# Power.net
KiCad netlist of a schematic drawn in Altium Designer
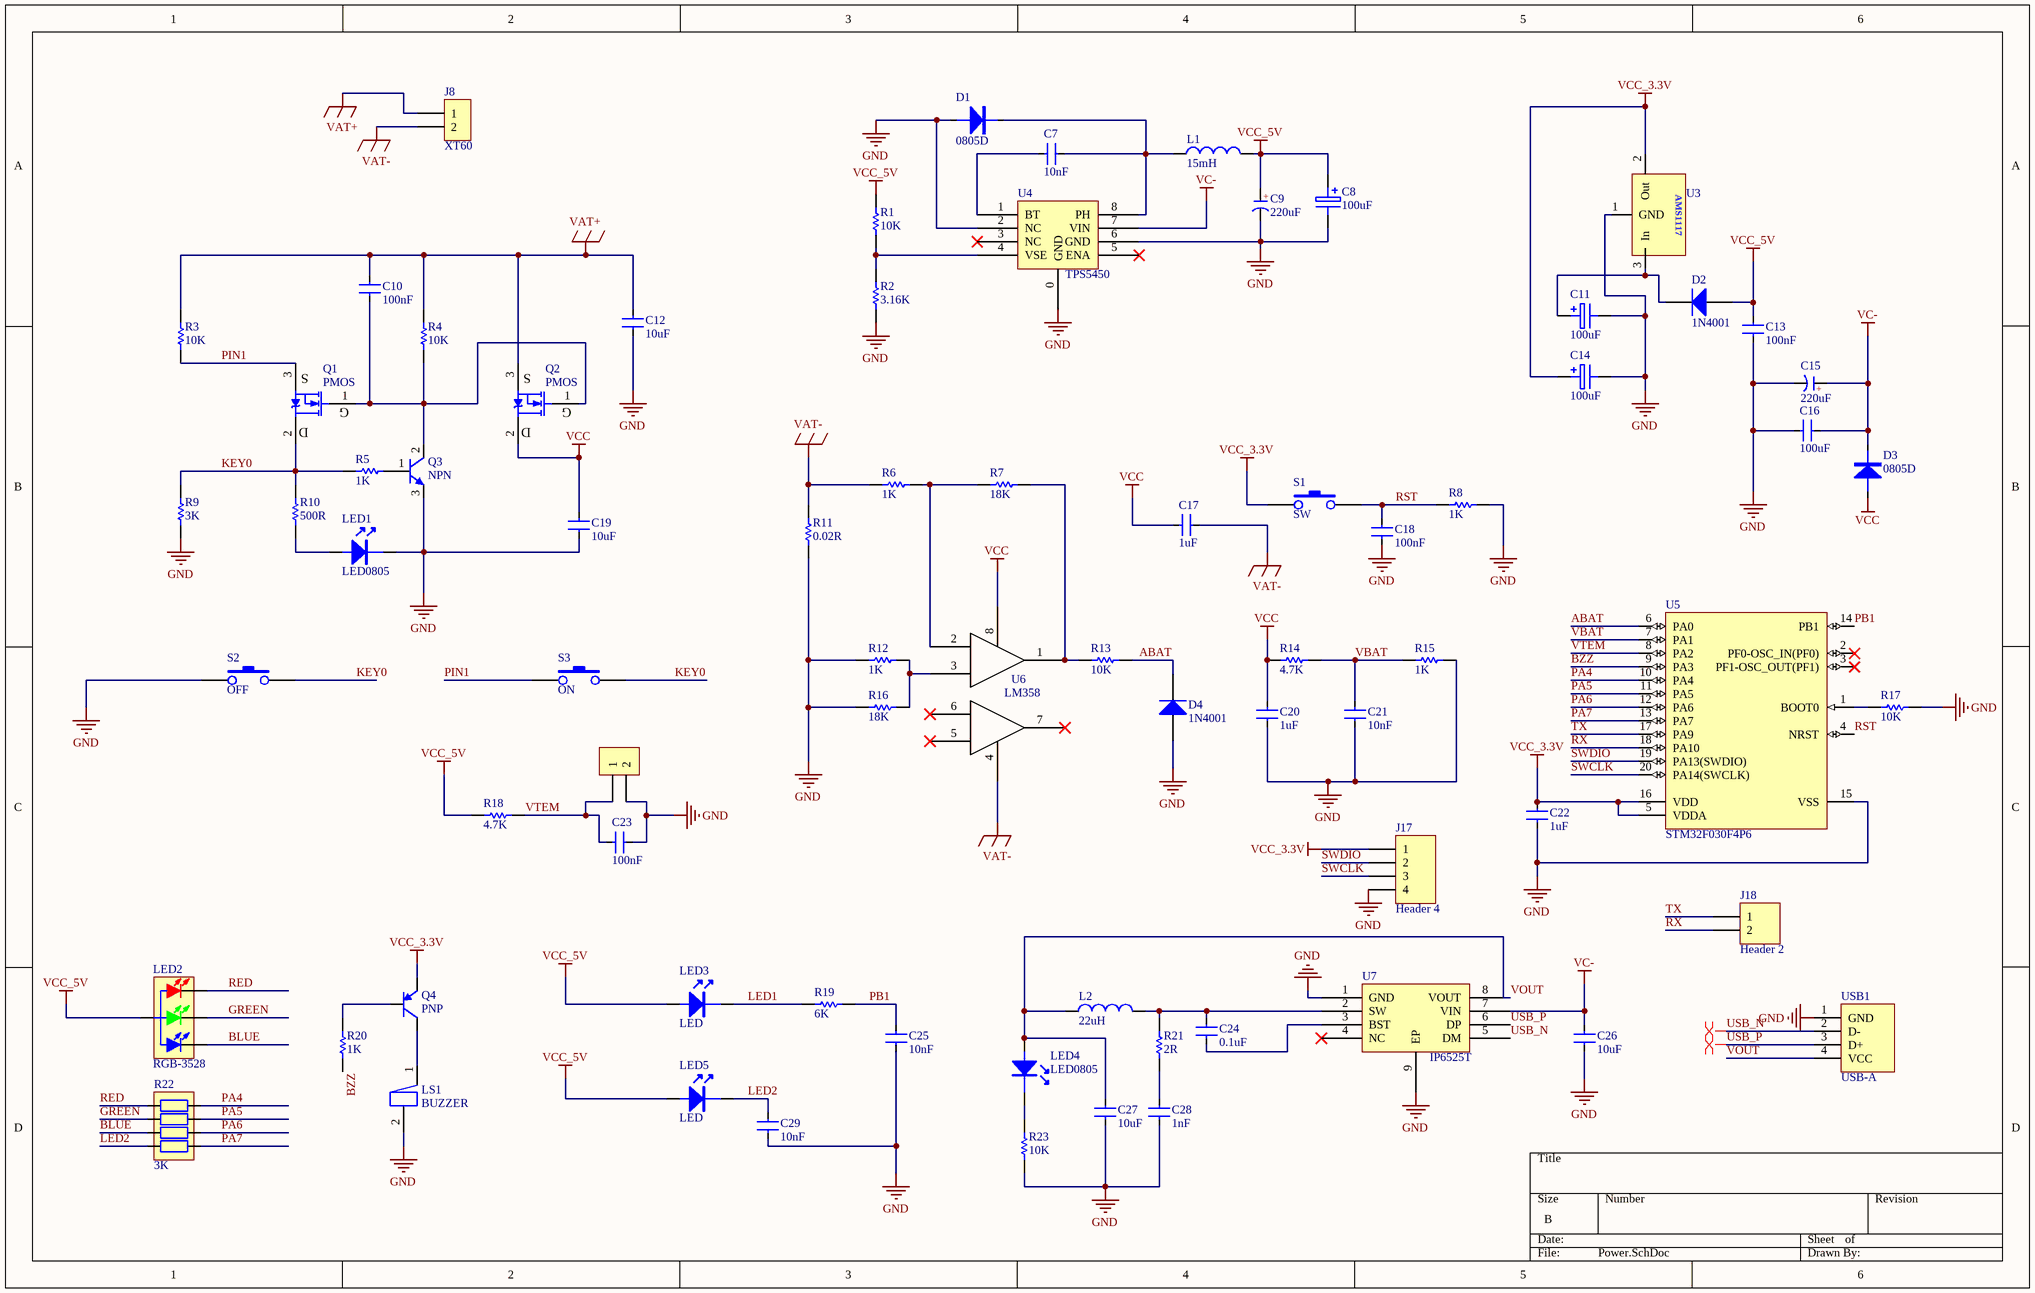
[diagram p0: Power.SchDoc]

(export (version "E")
  (design (tool "Eeschema 10.0.6"))
  (components
    (comp (ref "C7") (value "10nF") (footprint "0603_C") (libsource (lib "电容") (part "C0805")))
    (comp (ref "C8")
      (value "100uF")
      (footprint "CASE-C_6032")
      (description "电解电容")
      (libsource (lib "常用器件") (part "CAP-E"))
    )
    (comp (ref "C9")
      (value "220uF")
      (footprint "CASE-E_7343")
      (description "直插固态电容")
      (fields (field (name "版权归属") "源创客"))
      (libsource (lib "") (part "C-CS_1"))
    )
    (comp (ref "C10") (value "100nF") (footprint "0603_C") (libsource (lib "电容") (part "C0805")))
    (comp (ref "C11")
      (value "100uF")
      (footprint "CASE-C_6032")
      (description "电解电容")
      (libsource (lib "常用器件") (part "CAP-E"))
    )
    (comp (ref "C12") (value "10uF") (footprint "1206_C") (libsource (lib "电容") (part "C0805")))
    (comp (ref "C13") (value "100nF") (footprint "0603_C") (libsource (lib "电容") (part "C0805")))
    (comp (ref "C14")
      (value "100uF")
      (footprint "CASE-B_3528")
      (description "电解电容")
      (libsource (lib "常用器件") (part "CAP-E"))
    )
    (comp (ref "C15")
      (value "220uF")
      (footprint "CASE-E_7343")
      (description "直插固态电容")
      (fields (field (name "版权归属") "源创客"))
      (libsource (lib "3.1   - 电阻-电容-电感") (part "C-CS"))
    )
    (comp (ref "C16") (value "100uF") (footprint "1206_C") (libsource (lib "电容") (part "C0805")))
    (comp (ref "C17") (value "1uF") (footprint "0603_C") (libsource (lib "电容") (part "C0805")))
    (comp (ref "C18") (value "100nF") (footprint "0603_C") (libsource (lib "电容") (part "C0805")))
    (comp (ref "C19") (value "10uF") (footprint "1206_C") (libsource (lib "电容") (part "C0805")))
    (comp (ref "C20") (value "1uF") (footprint "0603_C") (libsource (lib "电容") (part "C0805")))
    (comp (ref "C21") (value "10nF") (footprint "0603_C") (libsource (lib "电容") (part "C0805")))
    (comp (ref "C22") (value "1uF") (footprint "0603_C") (libsource (lib "电容") (part "C0805")))
    (comp (ref "C23") (value "100nF") (footprint "0603_C") (libsource (lib "电容") (part "C0805")))
    (comp (ref "C24") (value "0.1uF") (footprint "0603_C") (libsource (lib "电容") (part "C0805")))
    (comp (ref "C25") (value "10nF") (footprint "0603_C") (libsource (lib "电容") (part "C0805")))
    (comp (ref "C26") (value "10uF") (footprint "1206_C") (libsource (lib "电容") (part "C0805")))
    (comp (ref "C27") (value "10uF") (footprint "0603_C") (libsource (lib "电容") (part "C0805")))
    (comp (ref "C28") (value "1nF") (footprint "0603_C") (libsource (lib "电容") (part "C0805")))
    (comp (ref "C29") (value "10nF") (footprint "0603_C") (libsource (lib "电容") (part "C0805")))
    (comp (ref "D1") (value "0805D") (footprint "SMB N") (libsource (lib "二极管") (part "0805D")))
    (comp (ref "D2")
      (value "Diode")
      (footprint "DIODE-1206")
      (description "二极管")
      (fields (field (name "TYPE") "1N4001") (field (name "PUBLISHER") "Altium Limited"))
      (libsource (lib "STM32单片机及常用原件") (part "Diode"))
    )
    (comp (ref "D3") (value "0805D") (footprint "SMB N") (libsource (lib "") (part "0805D_1")))
    (comp (ref "D4")
      (value "Diode")
      (footprint "DIODE-1206")
      (description "二极管")
      (fields (field (name "TYPE") "1N4001") (field (name "PUBLISHER") "Altium Limited"))
      (libsource (lib "STM32单片机及常用原件") (part "Diode"))
    )
    (comp (ref "J8") (value "XT60") (footprint "TX60-LI-S") (libsource (lib "插接件") (part "FD-SIP2")))
    (comp (ref "J17")
      (value "Header 4")
      (footprint "XH2.54-WI-4P")
      (description "Header, 4-Pin")
      (fields (field (name "PUBLISHER") "Altium Limited"))
      (libsource (lib "Miscellaneous Connectors") (part "Header 4"))
    )
    (comp (ref "J18")
      (value "Header 2")
      (footprint "XH2.54-LI-2P")
      (description "Header, 2-Pin")
      (fields (field (name "PUBLISHER") "Altium Limited"))
      (libsource (lib "Miscellaneous Connectors") (part "Header 2"))
    )
    (comp (ref "J？1") (value "XT60") (footprint "LC-0805_R") (libsource (lib "") (part "FD-SIP2_1")))
    (comp (ref "L1")
      (value "15mH")
      (footprint "IND-SMD_L6.0-W6.0_FNR60XXS")
      (libsource (lib "电感") (part "贴片电感"))
    )
    (comp (ref "L2")
      (value "22uH")
      (footprint "IND-SMD_L6.0-W6.0_FNR60XXS")
      (libsource (lib "电感") (part "贴片电感"))
    )
    (comp (ref "LED1")
      (value "LED0805")
      (footprint "LC-0603_LED_S1")
      (libsource (lib "LED or LCD") (part "LED0805"))
    )
    (comp (ref "LED2")
      (value "RGB-3528")
      (footprint "RGB-3528")
      (description "三基色LED")
      (fields (field (name "版权归属") "源创客"))
      (libsource (lib "9.1   - LED") (part "LED-RGB-3528"))
    )
    (comp (ref "LED3")
      (value "LED")
      (footprint "LC-0603_LED_S1")
      (libsource (lib "LED or LCD") (part "LED0805"))
    )
    (comp (ref "LED4")
      (value "LED0805")
      (footprint "LC-0603_LED_S1")
      (libsource (lib "LED or LCD") (part "LED0805"))
    )
    (comp (ref "LED5")
      (value "LED")
      (footprint "LC-0603_LED_S1")
      (libsource (lib "LED or LCD") (part "LED0805"))
    )
    (comp (ref "LS1") (value "BUZZER") (footprint "Beep") (libsource (lib "常用器件") (part "BUZZER")))
    (comp (ref "Q1")
      (value "PMOS")
      (footprint "TO-252-2-180")
      (description "N沟场效应管")
      (fields (field (name "版权归属") "源创客"))
      (libsource (lib "6.1   - 场效应管-可控硅") (part "P40NF10L"))
    )
    (comp (ref "Q2")
      (value "PMOS")
      (footprint "TO-252-2-180")
      (description "N沟场效应管")
      (fields (field (name "版权归属") "源创客"))
      (libsource (lib "6.1   - 场效应管-可控硅") (part "P40NF10L"))
    )
    (comp (ref "Q3")
      (value "NPN")
      (footprint "SOT-23(SOT-23-3)")
      (description "互补功率-NPN型")
      (fields (field (name "版权归属") "源创客"))
      (libsource (lib "6.2   - 三极管") (part "44H11"))
    )
    (comp (ref "Q4")
      (value "PNP")
      (footprint "SOT-23(SOT-23-3)")
      (description "互补功率-PNP型")
      (fields (field (name "版权归属") "源创客"))
      (libsource (lib "6.2   - 三极管") (part "TIP42C"))
    )
    (comp (ref "R1")
      (value "10K")
      (footprint "0603_R")
      (description "Resistor")
      (fields (field (name "PUBLISHER") "Altium Limited"))
      (libsource (lib "Miscellaneous Devices") (part "Res1"))
    )
    (comp (ref "R2")
      (value "3.16K")
      (footprint "0603_R")
      (description "Resistor")
      (fields (field (name "PUBLISHER") "Altium Limited"))
      (libsource (lib "Miscellaneous Devices") (part "Res1"))
    )
    (comp (ref "R3")
      (value "10K")
      (footprint "0603_R")
      (description "Resistor")
      (fields (field (name "PUBLISHER") "Altium Limited"))
      (libsource (lib "Miscellaneous Devices") (part "Res1"))
    )
    (comp (ref "R4")
      (value "10K")
      (footprint "0603_R")
      (description "Resistor")
      (fields (field (name "PUBLISHER") "Altium Limited"))
      (libsource (lib "Miscellaneous Devices") (part "Res1"))
    )
    (comp (ref "R5")
      (value "1K")
      (footprint "0603_R")
      (description "Resistor")
      (fields (field (name "PUBLISHER") "Altium Limited"))
      (libsource (lib "Miscellaneous Devices") (part "Res1"))
    )
    (comp (ref "R6")
      (value "1K")
      (footprint "0603_R")
      (description "Resistor")
      (fields (field (name "PUBLISHER") "Altium Limited"))
      (libsource (lib "Miscellaneous Devices") (part "Res1"))
    )
    (comp (ref "R7")
      (value "18K")
      (footprint "0603_R")
      (description "Resistor")
      (fields (field (name "PUBLISHER") "Altium Limited"))
      (libsource (lib "Miscellaneous Devices") (part "Res1"))
    )
    (comp (ref "R8")
      (value "1K")
      (footprint "0603_R")
      (description "Resistor")
      (fields (field (name "PUBLISHER") "Altium Limited"))
      (libsource (lib "Miscellaneous Devices") (part "Res1"))
    )
    (comp (ref "R9")
      (value "3K")
      (footprint "0603_R")
      (description "Resistor")
      (fields (field (name "PUBLISHER") "Altium Limited"))
      (libsource (lib "Miscellaneous Devices") (part "Res1"))
    )
    (comp (ref "R10")
      (value "500R")
      (footprint "0603_R")
      (description "Resistor")
      (fields (field (name "PUBLISHER") "Altium Limited"))
      (libsource (lib "Miscellaneous Devices") (part "Res1"))
    )
    (comp (ref "R11")
      (value "0.02R")
      (footprint "2512_R")
      (description "Resistor")
      (fields (field (name "PUBLISHER") "Altium Limited"))
      (libsource (lib "Miscellaneous Devices") (part "Res1"))
    )
    (comp (ref "R12")
      (value "1K")
      (footprint "0603_R")
      (description "Resistor")
      (fields (field (name "PUBLISHER") "Altium Limited"))
      (libsource (lib "Miscellaneous Devices") (part "Res1"))
    )
    (comp (ref "R13")
      (value "10K")
      (footprint "0603_R")
      (description "Resistor")
      (fields (field (name "PUBLISHER") "Altium Limited"))
      (libsource (lib "Miscellaneous Devices") (part "Res1"))
    )
    (comp (ref "R14")
      (value "4.7K")
      (footprint "0603_R")
      (description "Resistor")
      (fields (field (name "PUBLISHER") "Altium Limited"))
      (libsource (lib "Miscellaneous Devices") (part "Res1"))
    )
    (comp (ref "R15")
      (value "1K")
      (footprint "0603_R")
      (description "Resistor")
      (fields (field (name "PUBLISHER") "Altium Limited"))
      (libsource (lib "Miscellaneous Devices") (part "Res1"))
    )
    (comp (ref "R16")
      (value "18K")
      (footprint "0603_R")
      (description "Resistor")
      (fields (field (name "PUBLISHER") "Altium Limited"))
      (libsource (lib "Miscellaneous Devices") (part "Res1"))
    )
    (comp (ref "R17")
      (value "10K")
      (footprint "0603_R")
      (description "Resistor")
      (libsource (lib "Miscellaneous Devices") (part "Res1"))
    )
    (comp (ref "R18")
      (value "4.7K")
      (footprint "0603_R")
      (description "Resistor")
      (fields (field (name "PUBLISHER") "Altium Limited"))
      (libsource (lib "Miscellaneous Devices") (part "Res1"))
    )
    (comp (ref "R19")
      (value "6K")
      (footprint "0603_R")
      (description "Resistor")
      (fields (field (name "PUBLISHER") "Altium Limited"))
      (libsource (lib "Miscellaneous Devices") (part "Res1"))
    )
    (comp (ref "R20")
      (value "1K")
      (footprint "0603_R")
      (description "Resistor")
      (fields (field (name "PUBLISHER") "Altium Limited"))
      (libsource (lib "Miscellaneous Devices") (part "Res1"))
    )
    (comp (ref "R21")
      (value "2R")
      (footprint "0603_R")
      (description "Resistor")
      (fields (field (name "PUBLISHER") "Altium Limited"))
      (libsource (lib "Miscellaneous Devices") (part "Res1"))
    )
    (comp (ref "R22")
      (value "3K")
      (footprint "0603_Rx4")
      (description "贴片网络排阻")
      (fields (field (name "版权归属") "源创客"))
      (libsource (lib "3.1   - 电阻-电容-电感") (part "R-8P4R"))
    )
    (comp (ref "R23")
      (value "10K")
      (footprint "0603_R")
      (description "Resistor")
      (fields (field (name "PUBLISHER") "Altium Limited"))
      (libsource (lib "Miscellaneous Devices") (part "Res1"))
    )
    (comp (ref "S1") (value "SW") (footprint "微动开关-1") (libsource (lib "开关") (part "微动开关")))
    (comp (ref "S2") (value "OFF") (footprint "微动开关-1") (libsource (lib "开关") (part "微动开关")))
    (comp (ref "S3") (value "ON") (footprint "微动开关-1") (libsource (lib "开关") (part "微动开关")))
    (comp (ref "U3") (value "AMS1117") (footprint "AMS1117") (libsource (lib "常用芯片") (part "AMS1117")))
    (comp (ref "U4")
      (value "TPS5450")
      (footprint "SOP-8_EP_150mil")
      (libsource (lib "ZH1.5") (part "Component_6"))
    )
    (comp (ref "U5")
      (value "STM32F030F4P6")
      (footprint "STM-TSSOP20_L")
      (libsource (lib "STMicroelectronics STM32 F0") (part "STM32F030F4P6"))
    )
    (comp (ref "U6")
      (value "LM358")
      (footprint "SOIC-8_208mil")
      (libsource (lib "ZH1.5") (part "Component_8"))
    )
    (comp (ref "U7") (value "IP6525T") (footprint "IP6525T") (libsource (lib "ZH1.5") (part "Component_7")))
    (comp (ref "USB1") (value "USB-A") (footprint "USB-A") (libsource (lib "插接件") (part "USB-A")))
  )
  (nets
    (net (code "1") (name "/ABAT") (class "Default")
      (node (ref "D4") (pin "2") (pinfunction "K_2") (pintype "passive"))
      (node (ref "R13") (pin "1") (pinfunction "1_1") (pintype "passive"))
      (node (ref "U5") (pin "6") (pinfunction "PA0_6") (pintype "bidirectional"))
    )
    (net (code "2") (name "/BLUE") (class "Default")
      (node (ref "LED2") (pin "3") (pinfunction "BULE_K_3") (pintype "passive"))
      (node (ref "R22") (pin "3") (pinfunction "3_3") (pintype "passive"))
    )
    (net (code "3") (name "/BZZ") (class "Default")
      (node (ref "R20") (pin "2") (pinfunction "2_2") (pintype "passive"))
      (node (ref "U5") (pin "9") (pinfunction "PA3_9") (pintype "bidirectional"))
    )
    (net (code "4") (name "/GREEN") (class "Default")
      (node (ref "LED2") (pin "2") (pinfunction "GREEN_K_2") (pintype "passive"))
      (node (ref "R22") (pin "2") (pinfunction "2_2") (pintype "passive"))
    )
    (net (code "5") (name "/KEY0") (class "Default")
      (node (ref "Q1") (pin "2") (pinfunction "D_2") (pintype "passive"))
      (node (ref "R10") (pin "2") (pinfunction "2_2") (pintype "passive"))
      (node (ref "R5") (pin "2") (pinfunction "2_2") (pintype "passive"))
      (node (ref "R9") (pin "2") (pinfunction "2_2") (pintype "passive"))
      (node (ref "S2") (pin "2") (pinfunction "2_2") (pintype "passive"))
      (node (ref "S3") (pin "2") (pinfunction "2_2") (pintype "passive"))
    )
    (net (code "6") (name "/LED1") (class "Default")
      (node (ref "LED3") (pin "K") (pinfunction "2_K") (pintype "passive"))
      (node (ref "R19") (pin "1") (pinfunction "1_1") (pintype "passive"))
    )
    (net (code "7") (name "/LED2") (class "Default")
      (node (ref "C29") (pin "1") (pinfunction "1_1") (pintype "passive"))
      (node (ref "LED5") (pin "K") (pinfunction "2_K") (pintype "passive"))
      (node (ref "R22") (pin "4") (pinfunction "4_4") (pintype "passive"))
    )
    (net (code "8") (name "/PA4") (class "Default")
      (node (ref "R22") (pin "8") (pinfunction "8_8") (pintype "passive"))
      (node (ref "U5") (pin "10") (pinfunction "PA4_10") (pintype "bidirectional"))
    )
    (net (code "9") (name "/PA5") (class "Default")
      (node (ref "R22") (pin "7") (pinfunction "7_7") (pintype "passive"))
      (node (ref "U5") (pin "11") (pinfunction "PA5_11") (pintype "bidirectional"))
    )
    (net (code "10") (name "/PA6") (class "Default")
      (node (ref "R22") (pin "6") (pinfunction "6_6") (pintype "passive"))
      (node (ref "U5") (pin "12") (pinfunction "PA6_12") (pintype "bidirectional"))
    )
    (net (code "11") (name "/PA7") (class "Default")
      (node (ref "R22") (pin "5") (pinfunction "5_5") (pintype "passive"))
      (node (ref "U5") (pin "13") (pinfunction "PA7_13") (pintype "bidirectional"))
    )
    (net (code "12") (name "/PB1") (class "Default")
      (node (ref "C25") (pin "1") (pinfunction "1_1") (pintype "passive"))
      (node (ref "R19") (pin "2") (pinfunction "2_2") (pintype "passive"))
      (node (ref "U5") (pin "14") (pinfunction "PB1_14") (pintype "bidirectional"))
    )
    (net (code "13") (name "/PIN1") (class "Default")
      (node (ref "Q1") (pin "3") (pinfunction "S_3") (pintype "passive"))
      (node (ref "R3") (pin "1") (pinfunction "1_1") (pintype "passive"))
      (node (ref "S3") (pin "1") (pinfunction "1_1") (pintype "passive"))
    )
    (net (code "14") (name "/RED") (class "Default")
      (node (ref "LED2") (pin "1") (pinfunction "RED_K_1") (pintype "passive"))
      (node (ref "R22") (pin "1") (pinfunction "1_1") (pintype "passive"))
    )
    (net (code "15") (name "/RST") (class "Default")
      (node (ref "C18") (pin "2") (pinfunction "2_2") (pintype "passive"))
      (node (ref "R8") (pin "1") (pinfunction "1_1") (pintype "passive"))
      (node (ref "S1") (pin "2") (pinfunction "2_2") (pintype "passive"))
      (node (ref "U5") (pin "4") (pinfunction "NRST_4") (pintype "bidirectional"))
    )
    (net (code "16") (name "/RX") (class "Default")
      (node (ref "J18") (pin "2") (pinfunction "2_2") (pintype "passive"))
      (node (ref "U5") (pin "18") (pinfunction "PA10_18") (pintype "bidirectional"))
    )
    (net (code "17") (name "/SWCLK") (class "Default")
      (node (ref "J17") (pin "3") (pinfunction "3_3") (pintype "passive"))
      (node (ref "U5") (pin "20") (pinfunction "PA14(SWCLK)_20") (pintype "bidirectional"))
    )
    (net (code "18") (name "/SWDIO") (class "Default")
      (node (ref "J17") (pin "2") (pinfunction "2_2") (pintype "passive"))
      (node (ref "U5") (pin "19") (pinfunction "PA13(SWDIO)_19") (pintype "bidirectional"))
    )
    (net (code "19") (name "/TX") (class "Default")
      (node (ref "J18") (pin "1") (pinfunction "1_1") (pintype "passive"))
      (node (ref "U5") (pin "17") (pinfunction "PA9_17") (pintype "bidirectional"))
    )
    (net (code "20") (name "/USB_N") (class "Default")
      (node (ref "U7") (pin "5") (pinfunction "DM_5") (pintype "passive"))
      (node (ref "USB1") (pin "2") (pinfunction "D-_2") (pintype "passive"))
    )
    (net (code "21") (name "/USB_P") (class "Default")
      (node (ref "U7") (pin "6") (pinfunction "DP_6") (pintype "passive"))
      (node (ref "USB1") (pin "3") (pinfunction "D+_3") (pintype "passive"))
    )
    (net (code "22") (name "/VBAT") (class "Default")
      (node (ref "C21") (pin "1") (pinfunction "1_1") (pintype "passive"))
      (node (ref "R14") (pin "1") (pinfunction "1_1") (pintype "passive"))
      (node (ref "R15") (pin "2") (pinfunction "2_2") (pintype "passive"))
      (node (ref "U5") (pin "7") (pinfunction "PA1_7") (pintype "bidirectional"))
    )
    (net (code "23") (name "/VOUT") (class "Default")
      (node (ref "C27") (pin "2") (pinfunction "2_2") (pintype "passive"))
      (node (ref "L2") (pin "1") (pinfunction "1_1") (pintype "passive"))
      (node (ref "LED4") (pin "A") (pinfunction "1_A") (pintype "passive"))
      (node (ref "U7") (pin "8") (pinfunction "VOUT_8") (pintype "passive"))
      (node (ref "USB1") (pin "4") (pinfunction "VCC_4") (pintype "passive"))
    )
    (net (code "24") (name "/VTEM") (class "Default")
      (node (ref "C23") (pin "2") (pinfunction "2_2") (pintype "passive"))
      (node (ref "J？1") (pin "1") (pinfunction "1_1") (pintype "passive"))
      (node (ref "R18") (pin "1") (pinfunction "1_1") (pintype "passive"))
      (node (ref "U5") (pin "8") (pinfunction "PA2_8") (pintype "bidirectional"))
    )
    (net (code "25") (name "GND") (class "Default")
      (node (ref "C11") (pin "2") (pinfunction "2_2") (pintype "passive"))
      (node (ref "C12") (pin "1") (pinfunction "1_1") (pintype "passive"))
      (node (ref "C13") (pin "1") (pinfunction "1_1") (pintype "passive"))
      (node (ref "C14") (pin "2") (pinfunction "2_2") (pintype "passive"))
      (node (ref "C15") (pin "2") (pinfunction "K_2") (pintype "passive"))
      (node (ref "C16") (pin "1") (pinfunction "1_1") (pintype "passive"))
      (node (ref "C18") (pin "1") (pinfunction "1_1") (pintype "passive"))
      (node (ref "C19") (pin "1") (pinfunction "1_1") (pintype "passive"))
      (node (ref "C20") (pin "1") (pinfunction "1_1") (pintype "passive"))
      (node (ref "C21") (pin "2") (pinfunction "2_2") (pintype "passive"))
      (node (ref "C22") (pin "1") (pinfunction "1_1") (pintype "passive"))
      (node (ref "C23") (pin "1") (pinfunction "1_1") (pintype "passive"))
      (node (ref "C25") (pin "2") (pinfunction "2_2") (pintype "passive"))
      (node (ref "C26") (pin "1") (pinfunction "1_1") (pintype "passive"))
      (node (ref "C27") (pin "1") (pinfunction "1_1") (pintype "passive"))
      (node (ref "C28") (pin "1") (pinfunction "1_1") (pintype "passive"))
      (node (ref "C29") (pin "2") (pinfunction "2_2") (pintype "passive"))
      (node (ref "C8") (pin "2") (pinfunction "2_2") (pintype "passive"))
      (node (ref "C9") (pin "2") (pinfunction "K_2") (pintype "passive"))
      (node (ref "D1") (pin "A") (pinfunction "1_A") (pintype "passive"))
      (node (ref "D4") (pin "1") (pinfunction "A_1") (pintype "passive"))
      (node (ref "J17") (pin "4") (pinfunction "4_4") (pintype "passive"))
      (node (ref "J？1") (pin "2") (pinfunction "2_2") (pintype "passive"))
      (node (ref "LED1") (pin "K") (pinfunction "2_K") (pintype "passive"))
      (node (ref "LS1") (pin "2") (pinfunction "-_2") (pintype "passive"))
      (node (ref "Q3") (pin "3") (pinfunction "E_3") (pintype "passive"))
      (node (ref "R11") (pin "1") (pinfunction "1_1") (pintype "passive"))
      (node (ref "R12") (pin "2") (pinfunction "2_2") (pintype "passive"))
      (node (ref "R15") (pin "1") (pinfunction "1_1") (pintype "passive"))
      (node (ref "R16") (pin "2") (pinfunction "2_2") (pintype "passive"))
      (node (ref "R17") (pin "2") (pinfunction "2_2") (pintype "passive"))
      (node (ref "R2") (pin "1") (pinfunction "1_1") (pintype "passive"))
      (node (ref "R23") (pin "1") (pinfunction "1_1") (pintype "passive"))
      (node (ref "R8") (pin "2") (pinfunction "2_2") (pintype "passive"))
      (node (ref "R9") (pin "1") (pinfunction "1_1") (pintype "passive"))
      (node (ref "S2") (pin "1") (pinfunction "1_1") (pintype "passive"))
      (node (ref "U3") (pin "1") (pinfunction "GND_1") (pintype "passive"))
      (node (ref "U4") (pin "0") (pinfunction "GND_0") (pintype "passive"))
      (node (ref "U4") (pin "2") (pinfunction "NC_2") (pintype "passive"))
      (node (ref "U4") (pin "6") (pinfunction "GND_6") (pintype "passive"))
      (node (ref "U5") (pin "15") (pinfunction "VSS_15") (pintype "power_in"))
      (node (ref "U7") (pin "1") (pinfunction "GND_1") (pintype "passive"))
      (node (ref "U7") (pin "9") (pinfunction "EP_9") (pintype "passive"))
      (node (ref "USB1") (pin "1") (pinfunction "GND_1") (pintype "passive"))
    )
    (net (code "26") (name "Net-(C28-Pad2)") (class "Default")
      (node (ref "C28") (pin "2") (pinfunction "2_2") (pintype "passive"))
      (node (ref "R21") (pin "1") (pinfunction "1_1") (pintype "passive"))
    )
    (net (code "27") (name "Net-(D1-2)") (class "Default")
      (node (ref "C7") (pin "2") (pinfunction "2_2") (pintype "passive"))
      (node (ref "D1") (pin "K") (pinfunction "2_K") (pintype "passive"))
      (node (ref "L1") (pin "1") (pinfunction "1_1") (pintype "passive"))
      (node (ref "U4") (pin "8") (pinfunction "PH_8") (pintype "passive"))
    )
    (net (code "28") (name "Net-(D2-K)") (class "Default")
      (node (ref "C11") (pin "1") (pinfunction "1_1") (pintype "passive"))
      (node (ref "D2") (pin "2") (pinfunction "K_2") (pintype "passive"))
      (node (ref "U3") (pin "3") (pinfunction "In_3") (pintype "passive"))
    )
    (net (code "29") (name "Net-(LED1-1)") (class "Default")
      (node (ref "LED1") (pin "A") (pinfunction "1_A") (pintype "passive"))
      (node (ref "R10") (pin "1") (pinfunction "1_1") (pintype "passive"))
    )
    (net (code "30") (name "Net-(LED4-2)") (class "Default")
      (node (ref "LED4") (pin "K") (pinfunction "2_K") (pintype "passive"))
      (node (ref "R23") (pin "2") (pinfunction "2_2") (pintype "passive"))
    )
    (net (code "31") (name "Net-(LS1-+)") (class "Default")
      (node (ref "LS1") (pin "1") (pinfunction "+_1") (pintype "passive"))
      (node (ref "Q4") (pin "2") (pinfunction "C_2") (pintype "passive"))
    )
    (net (code "32") (name "Net-(Q1-G)") (class "Default")
      (node (ref "C10") (pin "1") (pinfunction "1_1") (pintype "passive"))
      (node (ref "Q1") (pin "1") (pinfunction "G_1") (pintype "passive"))
      (node (ref "Q2") (pin "1") (pinfunction "G_1") (pintype "passive"))
      (node (ref "Q3") (pin "2") (pinfunction "C_2") (pintype "passive"))
      (node (ref "R4") (pin "1") (pinfunction "1_1") (pintype "passive"))
    )
    (net (code "33") (name "Net-(Q3-B)") (class "Default")
      (node (ref "Q3") (pin "1") (pinfunction "B_1") (pintype "passive"))
      (node (ref "R5") (pin "1") (pinfunction "1_1") (pintype "passive"))
    )
    (net (code "34") (name "Net-(Q4-B)") (class "Default")
      (node (ref "Q4") (pin "1") (pinfunction "B_1") (pintype "passive"))
      (node (ref "R20") (pin "1") (pinfunction "1_1") (pintype "passive"))
    )
    (net (code "35") (name "Net-(R6-Pad1)") (class "Default")
      (node (ref "R6") (pin "1") (pinfunction "1_1") (pintype "passive"))
      (node (ref "R7") (pin "2") (pinfunction "2_2") (pintype "passive"))
      (node (ref "U6") (pin "2") (pinfunction "2_2") (pintype "passive"))
    )
    (net (code "36") (name "Net-(R12-Pad1)") (class "Default")
      (node (ref "R12") (pin "1") (pinfunction "1_1") (pintype "passive"))
      (node (ref "R16") (pin "1") (pinfunction "1_1") (pintype "passive"))
      (node (ref "U6") (pin "3") (pinfunction "3_3") (pintype "passive"))
    )
    (net (code "37") (name "Net-(R13-Pad2)") (class "Default")
      (node (ref "R13") (pin "2") (pinfunction "2_2") (pintype "passive"))
      (node (ref "R7") (pin "1") (pinfunction "1_1") (pintype "passive"))
      (node (ref "U6") (pin "1") (pinfunction "1_1") (pintype "passive"))
    )
    (net (code "38") (name "Net-(U4-BT)") (class "Default")
      (node (ref "C7") (pin "1") (pinfunction "1_1") (pintype "passive"))
      (node (ref "U4") (pin "1") (pinfunction "BT_1") (pintype "passive"))
    )
    (net (code "39") (name "Net-(U4-VSE)") (class "Default")
      (node (ref "R1") (pin "1") (pinfunction "1_1") (pintype "passive"))
      (node (ref "R2") (pin "2") (pinfunction "2_2") (pintype "passive"))
      (node (ref "U4") (pin "4") (pinfunction "VSE_4") (pintype "passive"))
    )
    (net (code "40") (name "Net-(U5-BOOT0)") (class "Default")
      (node (ref "R17") (pin "1") (pinfunction "1_1") (pintype "passive"))
      (node (ref "U5") (pin "1") (pinfunction "BOOT0_1") (pintype "input"))
    )
    (net (code "41") (name "Net-(U7-BST)") (class "Default")
      (node (ref "C24") (pin "1") (pinfunction "1_1") (pintype "passive"))
      (node (ref "U7") (pin "3") (pinfunction "BST_3") (pintype "passive"))
    )
    (net (code "42") (name "Net-(U7-SW)") (class "Default")
      (node (ref "C24") (pin "2") (pinfunction "2_2") (pintype "passive"))
      (node (ref "L2") (pin "2") (pinfunction "2_2") (pintype "passive"))
      (node (ref "R21") (pin "2") (pinfunction "2_2") (pintype "passive"))
      (node (ref "U7") (pin "2") (pinfunction "SW_2") (pintype "passive"))
    )
    (net (code "43") (name "VAT+") (class "Default")
      (node (ref "C10") (pin "2") (pinfunction "2_2") (pintype "passive"))
      (node (ref "C12") (pin "2") (pinfunction "2_2") (pintype "passive"))
      (node (ref "J8") (pin "1") (pinfunction "1_1") (pintype "passive"))
      (node (ref "Q2") (pin "3") (pinfunction "S_3") (pintype "passive"))
      (node (ref "R3") (pin "2") (pinfunction "2_2") (pintype "passive"))
      (node (ref "R4") (pin "2") (pinfunction "2_2") (pintype "passive"))
    )
    (net (code "44") (name "VAT-") (class "Default")
      (node (ref "C17") (pin "1") (pinfunction "1_1") (pintype "passive"))
      (node (ref "J8") (pin "2") (pinfunction "2_2") (pintype "passive"))
      (node (ref "R11") (pin "2") (pinfunction "2_2") (pintype "passive"))
      (node (ref "R6") (pin "2") (pinfunction "2_2") (pintype "passive"))
      (node (ref "U6") (pin "4") (pinfunction "4_4") (pintype "passive"))
    )
    (net (code "45") (name "VC-") (class "Default")
      (node (ref "C15") (pin "1") (pinfunction "A_1") (pintype "passive"))
      (node (ref "C16") (pin "2") (pinfunction "2_2") (pintype "passive"))
      (node (ref "C26") (pin "2") (pinfunction "2_2") (pintype "passive"))
      (node (ref "D3") (pin "K") (pinfunction "2_K") (pintype "passive"))
      (node (ref "U4") (pin "7") (pinfunction "VIN_7") (pintype "passive"))
      (node (ref "U7") (pin "7") (pinfunction "VIN_7") (pintype "passive"))
    )
    (net (code "46") (name "VCC") (class "Default")
      (node (ref "C17") (pin "2") (pinfunction "2_2") (pintype "passive"))
      (node (ref "C19") (pin "2") (pinfunction "2_2") (pintype "passive"))
      (node (ref "C20") (pin "2") (pinfunction "2_2") (pintype "passive"))
      (node (ref "D3") (pin "A") (pinfunction "1_A") (pintype "passive"))
      (node (ref "Q2") (pin "2") (pinfunction "D_2") (pintype "passive"))
      (node (ref "R14") (pin "2") (pinfunction "2_2") (pintype "passive"))
      (node (ref "U6") (pin "8") (pinfunction "8_8") (pintype "passive"))
    )
    (net (code "47") (name "VCC_3.3V") (class "Default")
      (node (ref "C14") (pin "1") (pinfunction "1_1") (pintype "passive"))
      (node (ref "C22") (pin "2") (pinfunction "2_2") (pintype "passive"))
      (node (ref "J17") (pin "1") (pinfunction "1_1") (pintype "passive"))
      (node (ref "Q4") (pin "3") (pinfunction "E_3") (pintype "passive"))
      (node (ref "S1") (pin "1") (pinfunction "1_1") (pintype "passive"))
      (node (ref "U3") (pin "2") (pinfunction "Out_2") (pintype "passive"))
      (node (ref "U5") (pin "16") (pinfunction "VDD_16") (pintype "power_in"))
      (node (ref "U5") (pin "5") (pinfunction "VDDA_5") (pintype "power_in"))
    )
    (net (code "48") (name "VCC_5V") (class "Default")
      (node (ref "C13") (pin "2") (pinfunction "2_2") (pintype "passive"))
      (node (ref "C8") (pin "1") (pinfunction "1_1") (pintype "passive"))
      (node (ref "C9") (pin "1") (pinfunction "A_1") (pintype "passive"))
      (node (ref "D2") (pin "1") (pinfunction "A_1") (pintype "passive"))
      (node (ref "L1") (pin "2") (pinfunction "2_2") (pintype "passive"))
      (node (ref "LED2") (pin "4") (pinfunction "A_4") (pintype "passive"))
      (node (ref "LED3") (pin "A") (pinfunction "1_A") (pintype "passive"))
      (node (ref "LED5") (pin "A") (pinfunction "1_A") (pintype "passive"))
      (node (ref "R1") (pin "2") (pinfunction "2_2") (pintype "passive"))
      (node (ref "R18") (pin "2") (pinfunction "2_2") (pintype "passive"))
    )
    (net (code "49") (name "unconnected-(U4-ENA-Pad5)") (class "Default")
      (node (ref "U4") (pin "5") (pinfunction "ENA_5") (pintype "passive+no_connect"))
    )
    (net (code "50") (name "unconnected-(U4-NC-Pad3)") (class "Default")
      (node (ref "U4") (pin "3") (pinfunction "NC_3") (pintype "passive+no_connect"))
    )
    (net (code "51") (name "unconnected-(U5-PF0-OSC_IN(PF0)-Pad2)") (class "Default")
      (node (ref "U5") (pin "2") (pinfunction "PF0-OSC_IN(PF0)_2") (pintype "bidirectional+no_connect"))
    )
    (net (code "52") (name "unconnected-(U5-PF1-OSC_OUT(PF1)-Pad3)") (class "Default")
      (node (ref "U5") (pin "3") (pinfunction "PF1-OSC_OUT(PF1)_3") (pintype "bidirectional+no_connect"))
    )
    (net (code "53") (name "unconnected-(U6-Pad5)") (class "Default")
      (node (ref "U6") (pin "5") (pinfunction "5_5") (pintype "passive+no_connect"))
    )
    (net (code "54") (name "unconnected-(U6-Pad6)") (class "Default")
      (node (ref "U6") (pin "6") (pinfunction "6_6") (pintype "passive+no_connect"))
    )
    (net (code "55") (name "unconnected-(U6-Pad7)") (class "Default")
      (node (ref "U6") (pin "7") (pinfunction "7_7") (pintype "passive+no_connect"))
    )
    (net (code "56") (name "unconnected-(U7-NC-Pad4)") (class "Default")
      (node (ref "U7") (pin "4") (pinfunction "NC_4") (pintype "passive+no_connect"))
    )
  )
)
